# UVEEC_LED_Cube.net
KiCad netlist of a schematic drawn in Altium Designer
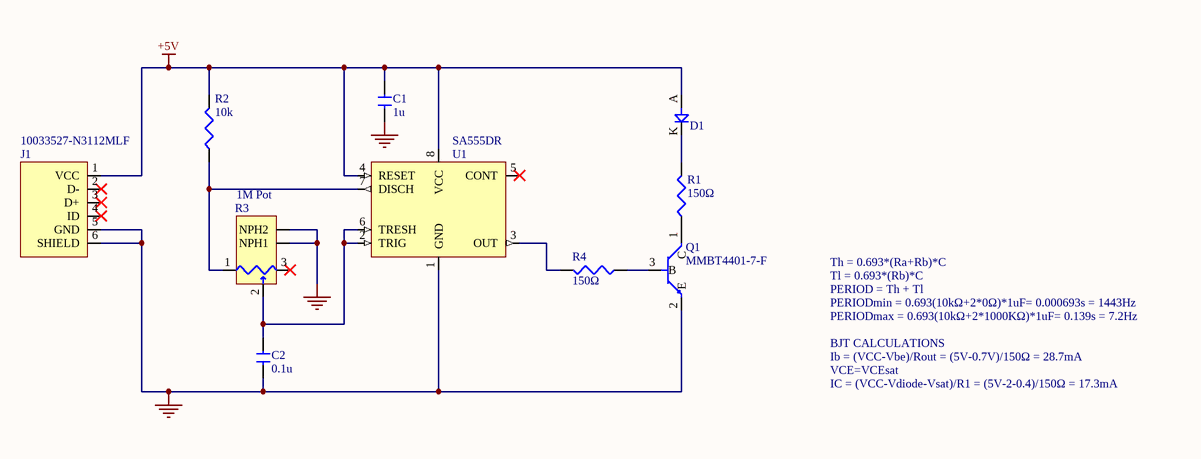
[diagram p0: UVEEC LED Cube.SchDoc]

(export (version "E")
  (design (tool "Eeschema 10.0.6"))
  (components
    (comp (ref "C1")
      (value "1u")
      (footprint "Capacitor 1206")
      (description "Cap Ceramic 1uF 25V X7R 10% SMD 1206 125°C Embossed T/R")
      (fields
        (field (name "MANUFACTURER") "Samsung")
        (field (name "MANUFACTURER PART NUMBER") "CL31B105KAHNFNE")
      )
      (libsource (lib "UVEEC LED Cube") (part "CL31B105KAHNFNE"))
    )
    (comp (ref "C2")
      (value "0.1u")
      (footprint "Capacitor 1206")
      (description "Multilayer Ceramic Capacitor, 0.1 uF, 50 V, ± 10%, X7R, 1206 [3216 Metric]")
      (fields
        (field (name "MANUFACTURER") "Samsung")
        (field (name "MANUFACTURER PART NUMBER") "CL31B104KBCNNNC")
      )
      (libsource (lib "UVEEC LED Cube") (part "CL31B104KBCNNNC"))
    )
    (comp (ref "D1")
      (value "HL3P-BF60-C00DD")
      (footprint "Diode TH D 1.05 P 2.54")
      (description "LED Yellow Green 570nm 20mA 2-Pin Through Hole T/R")
      (fields (field (name "MANUFACTURER") "Broadcom"))
      (libsource (lib "UVEEC LED Cube") (part "HL3P-BF60-C00DD"))
    )
    (comp (ref "J1")
      (value "10033527-N3112MLF")
      (footprint "10033527-N3112MLF")
      (description "MINI USB 2.0- AB Type Receptacle conn. Right Angle Surface Mount Type")
      (fields (field (name "MANUFACTURER") "Amphenol ICC / FCI"))
      (libsource (lib "UVEEC LED Cube") (part "10033527-N3112MLF"))
    )
    (comp (ref "Q1")
      (value "MMBT4401-7-F")
      (footprint "SOT-23-3")
      (description "NPN Ic=600mA Vceo=40V hfe=100~300 fT=250MHz P=310mW SOT-23")
      (fields (field (name "MANUFACTURER") "Diodes"))
      (libsource (lib "UVEEC LED Cube") (part "MMBT4401-7-F"))
    )
    (comp (ref "R1")
      (value "150Ω")
      (footprint "Resistor 1206")
      (description "RES 150 OHM 1% 1/4W 1206")
      (fields
        (field (name "MANUFACTURER") "Stackpole Electronics")
        (field (name "MANUFACTURER PART NUMBER") "RMCF1206FG150R")
      )
      (libsource (lib "UVEEC LED Cube") (part "RMCF1206FG150R"))
    )
    (comp (ref "R2")
      (value "10k")
      (footprint "Resistor 1206")
      (description "Res Thick Film 1206 10K Ohm 1% 0.25W ±100ppm/°C Molded SMD Paper T/R")
      (fields
        (field (name "MANUFACTURER") "Stackpole Electronics")
        (field (name "MANUFACTURER PART NUMBER") "RMCF1206FT10K0")
      )
      (libsource (lib "UVEEC LED Cube") (part "RMCF1206FT10K0"))
    )
    (comp (ref "R3")
      (value "1M Pot")
      (footprint "PDB12-H4301-105BF")
      (fields
        (field (name "MANUFACTURER") "Bourns")
        (field (name "MANUFACTURER PART NUMBER") "PDB12-H4301-105BF")
        (field (name "TOLERANCE") "20%")
      )
      (libsource (lib "UVEEC LED Cube") (part "PDB12-H4301-105BF"))
    )
    (comp (ref "R4")
      (value "150Ω")
      (footprint "Resistor 1206")
      (description "RES 150 OHM 1% 1/4W 1206")
      (fields
        (field (name "MANUFACTURER") "Stackpole Electronics")
        (field (name "MANUFACTURER PART NUMBER") "RMCF1206FG150R")
      )
      (libsource (lib "UVEEC LED Cube") (part "RMCF1206FG150R"))
    )
    (comp (ref "U1")
      (value "SA555DR")
      (footprint "SOIC-8")
      (description "IC OSC SGL TIMER 100KHZ 8-SOIC")
      (fields (field (name "MANUFACTURER") "Texas Instruments"))
      (libsource (lib "UVEEC LED Cube") (part "SA555DR"))
    )
  )
  (nets
    (net (code "1") (name "+5V") (class "Default")
      (node (ref "C1") (pin "1") (pinfunction "1_1") (pintype "passive"))
      (node (ref "D1") (pin "A") (pinfunction "A_A") (pintype "passive"))
      (node (ref "J1") (pin "1") (pinfunction "VCC_1") (pintype "passive"))
      (node (ref "R2") (pin "2") (pinfunction "2_2") (pintype "passive"))
      (node (ref "U1") (pin "4") (pinfunction "RESET_4") (pintype "input"))
      (node (ref "U1") (pin "8") (pinfunction "VCC_8") (pintype "power_in"))
    )
    (net (code "2") (name "GND") (class "Default")
      (node (ref "C1") (pin "2") (pinfunction "2_2") (pintype "passive"))
      (node (ref "C2") (pin "2") (pinfunction "2_2") (pintype "passive"))
      (node (ref "J1") (pin "5") (pinfunction "GND_5") (pintype "passive"))
      (node (ref "J1") (pin "6") (pinfunction "SHIELD_6") (pintype "passive"))
      (node (ref "Q1") (pin "2") (pinfunction "E_2") (pintype "passive"))
      (node (ref "R3") (pin "NPH1") (pinfunction "NPH1_NPH1") (pintype "passive"))
      (node (ref "R3") (pin "NPH2") (pinfunction "NPH2_NPH2") (pintype "passive"))
      (node (ref "U1") (pin "1") (pinfunction "GND_1") (pintype "power_in"))
    )
    (net (code "3") (name "Net-(D1-PadK)") (class "Default")
      (node (ref "D1") (pin "K") (pinfunction "K_K") (pintype "passive"))
      (node (ref "R1") (pin "2") (pinfunction "2_2") (pintype "passive"))
    )
    (net (code "4") (name "Net-(Q1-B)") (class "Default")
      (node (ref "Q1") (pin "3") (pinfunction "B_3") (pintype "passive"))
      (node (ref "R4") (pin "1") (pinfunction "1_1") (pintype "passive"))
    )
    (net (code "5") (name "Net-(Q1-C)") (class "Default")
      (node (ref "Q1") (pin "1") (pinfunction "C_1") (pintype "passive"))
      (node (ref "R1") (pin "1") (pinfunction "1_1") (pintype "passive"))
    )
    (net (code "6") (name "Net-(R3-CCW)") (class "Default")
      (node (ref "R2") (pin "1") (pinfunction "1_1") (pintype "passive"))
      (node (ref "R3") (pin "1") (pinfunction "CCW_1") (pintype "passive"))
      (node (ref "U1") (pin "7") (pinfunction "DISCH_7") (pintype "output"))
    )
    (net (code "7") (name "Net-(R3-WIPER)") (class "Default")
      (node (ref "C2") (pin "1") (pinfunction "1_1") (pintype "passive"))
      (node (ref "R3") (pin "2") (pinfunction "WIPER_2") (pintype "passive"))
      (node (ref "U1") (pin "2") (pinfunction "TRIG_2") (pintype "input"))
      (node (ref "U1") (pin "6") (pinfunction "TRESH_6") (pintype "input"))
    )
    (net (code "8") (name "Net-(U1-OUT)") (class "Default")
      (node (ref "R4") (pin "2") (pinfunction "2_2") (pintype "passive"))
      (node (ref "U1") (pin "3") (pinfunction "OUT_3") (pintype "output"))
    )
    (net (code "9") (name "unconnected-(J1-D+-Pad3)") (class "Default")
      (node (ref "J1") (pin "3") (pinfunction "D+_3") (pintype "passive+no_connect"))
    )
    (net (code "10") (name "unconnected-(J1-D--Pad2)") (class "Default")
      (node (ref "J1") (pin "2") (pinfunction "D-_2") (pintype "passive+no_connect"))
    )
    (net (code "11") (name "unconnected-(J1-ID-Pad4)") (class "Default")
      (node (ref "J1") (pin "4") (pinfunction "ID_4") (pintype "passive+no_connect"))
    )
    (net (code "12") (name "unconnected-(R3-CW-Pad3)") (class "Default")
      (node (ref "R3") (pin "3") (pinfunction "CW_3") (pintype "passive+no_connect"))
    )
    (net (code "13") (name "unconnected-(U1-CONT-Pad5)") (class "Default")
      (node (ref "U1") (pin "5") (pinfunction "CONT_5") (pintype "bidirectional+no_connect"))
    )
  )
)
